# DM3370_EEPROM_Add.net
KiCad netlist of a schematic drawn in Altium Designer
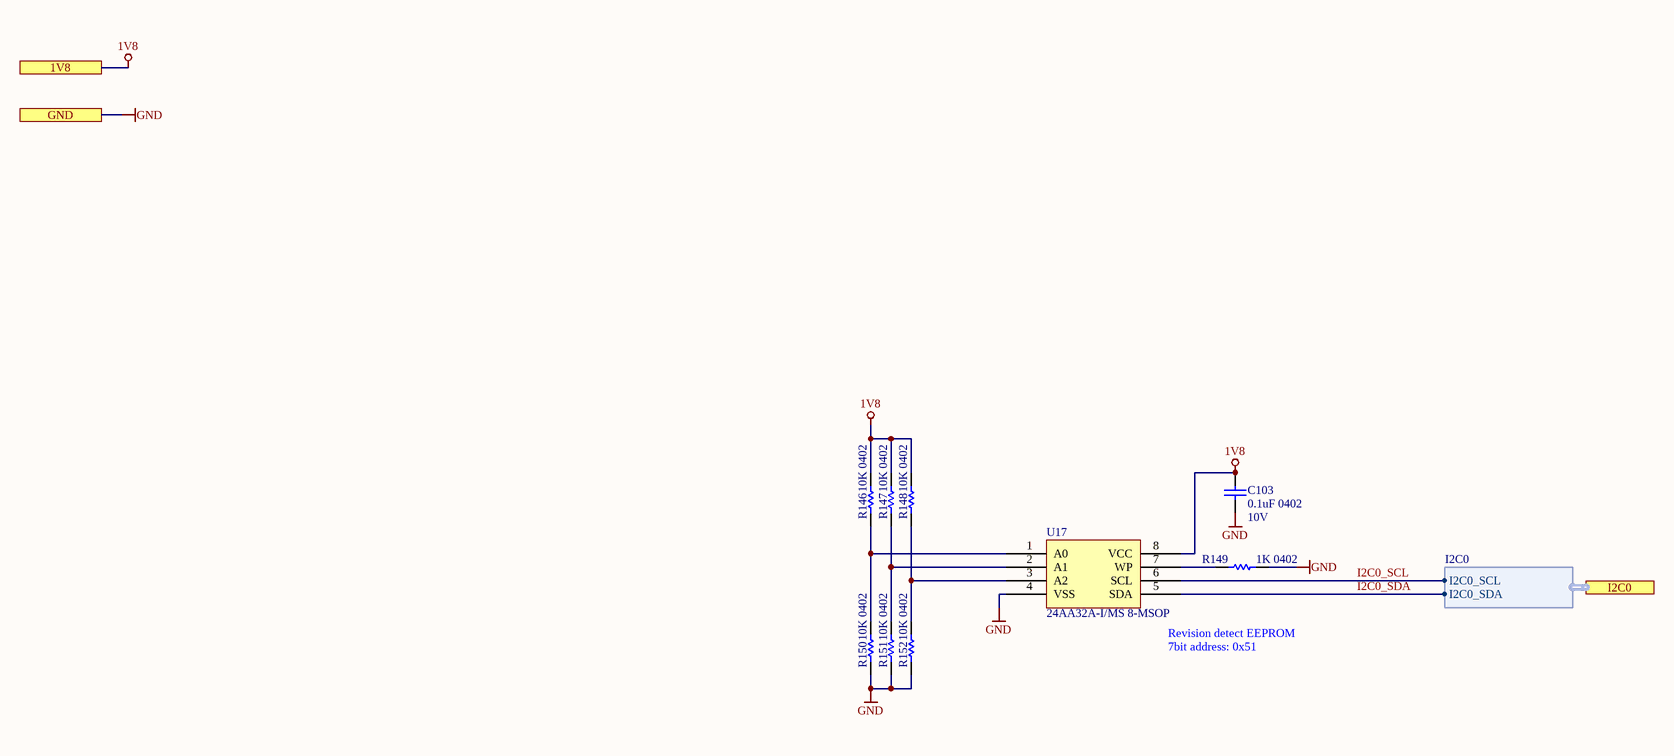
[diagram p0: DM3370_EEPROM_Add.SchDoc]

(export (version "E")
  (design (tool "Eeschema 10.0.6"))
  (components
    (comp (ref "C103")
      (value "0.1uF 0402")
      (footprint "CAP_Altium_Vault_Generic:CAPC0402(1005)70_L")
      (description "CAP CER 0.1UF 10V X7R 0402 5%")
      (fields (field (name "TOLERANCE") "5%") (field (name "VOLTAGE RATING") "10V"))
      (libsource (lib "LuxonisMaster") (part "GRM155R71A104JA01D"))
    )
    (comp (ref "R146")
      (value "10K 0402")
      (footprint "RES_Altium_Vault_Generic:RESC0402(1005)_L")
      (fields (field (name "TOLERANCE") "1%"))
      (libsource (lib "LuxonisMaster") (part "RC0402FR-1310KL"))
    )
    (comp (ref "R147")
      (value "10K 0402")
      (footprint "RES_Altium_Vault_Generic:RESC0402(1005)_L")
      (fields (field (name "TOLERANCE") "1%"))
      (libsource (lib "LuxonisMaster") (part "RC0402FR-1310KL"))
    )
    (comp (ref "R148")
      (value "10K 0402")
      (footprint "RES_Altium_Vault_Generic:RESC0402(1005)_L")
      (fields (field (name "TOLERANCE") "1%"))
      (libsource (lib "LuxonisMaster") (part "RC0402FR-1310KL"))
    )
    (comp (ref "R149")
      (value "1K 0402")
      (footprint "RES_Altium_Vault_Generic:RESC0402(1005)_L")
      (description "RES SMD 1K OHM 1% 1/16W 0402")
      (fields (field (name "TOLERANCE") "1%"))
      (libsource (lib "LuxonisMaster") (part "RC0402FR-071KL"))
    )
    (comp (ref "R150")
      (value "10K 0402")
      (footprint "RES_Altium_Vault_Generic:RESC0402(1005)_L")
      (fields (field (name "TOLERANCE") "1%"))
      (libsource (lib "LuxonisMaster") (part "RC0402FR-1310KL"))
    )
    (comp (ref "R151")
      (value "10K 0402")
      (footprint "RES_Altium_Vault_Generic:RESC0402(1005)_L")
      (fields (field (name "TOLERANCE") "1%"))
      (libsource (lib "LuxonisMaster") (part "RC0402FR-1310KL"))
    )
    (comp (ref "R152")
      (value "10K 0402")
      (footprint "RES_Altium_Vault_Generic:RESC0402(1005)_L")
      (fields (field (name "TOLERANCE") "1%"))
      (libsource (lib "LuxonisMaster") (part "RC0402FR-1310KL"))
    )
    (comp (ref "U17")
      (value "24AA32A-I/MS 8-MSOP")
      (footprint "LuxonisMaster:24AA32A-I/MS")
      (description "IC EEPROM 32K I2C 400KHZ 8MSOP Memory IC 32Kb (4K x 8) I²C 400kHz 900ns 8-MSOP")
      (libsource (lib "LuxonisMaster") (part "24AA32A-I/MS"))
    )
  )
  (nets
    (net (code "2") (name "/I2C0_SCL") (class "Default")
      (node (ref "U17") (pin "6") (pinfunction "SCL_6") (pintype "passive"))
    )
    (net (code "3") (name "/I2C0_SDA") (class "Default")
      (node (ref "U17") (pin "5") (pinfunction "SDA_5") (pintype "passive"))
    )
    (net (code "5") (name "1V8") (class "Default")
      (node (ref "C103") (pin "2") (pinfunction "2_2") (pintype "passive"))
      (node (ref "R146") (pin "2") (pinfunction "2_2") (pintype "passive"))
      (node (ref "R147") (pin "2") (pinfunction "2_2") (pintype "passive"))
      (node (ref "R148") (pin "2") (pinfunction "2_2") (pintype "passive"))
      (node (ref "U17") (pin "8") (pinfunction "VCC_8") (pintype "passive"))
    )
    (net (code "6") (name "GND") (class "Default")
      (node (ref "C103") (pin "1") (pinfunction "1_1") (pintype "passive"))
      (node (ref "R149") (pin "1") (pinfunction "1_1") (pintype "passive"))
      (node (ref "R150") (pin "1") (pinfunction "1_1") (pintype "passive"))
      (node (ref "R151") (pin "1") (pinfunction "1_1") (pintype "passive"))
      (node (ref "R152") (pin "1") (pinfunction "1_1") (pintype "passive"))
      (node (ref "U17") (pin "4") (pinfunction "VSS_4") (pintype "passive"))
    )
    (net (code "7") (name "Net-(U17-A0)") (class "Default")
      (node (ref "R146") (pin "1") (pinfunction "1_1") (pintype "passive"))
      (node (ref "R150") (pin "2") (pinfunction "2_2") (pintype "passive"))
      (node (ref "U17") (pin "1") (pinfunction "A0_1") (pintype "passive"))
    )
    (net (code "8") (name "Net-(U17-A1)") (class "Default")
      (node (ref "R147") (pin "1") (pinfunction "1_1") (pintype "passive"))
      (node (ref "R151") (pin "2") (pinfunction "2_2") (pintype "passive"))
      (node (ref "U17") (pin "2") (pinfunction "A1_2") (pintype "passive"))
    )
    (net (code "9") (name "Net-(U17-A2)") (class "Default")
      (node (ref "R148") (pin "1") (pinfunction "1_1") (pintype "passive"))
      (node (ref "R152") (pin "2") (pinfunction "2_2") (pintype "passive"))
      (node (ref "U17") (pin "3") (pinfunction "A2_3") (pintype "passive"))
    )
    (net (code "10") (name "Net-(U17-WP)") (class "Default")
      (node (ref "R149") (pin "2") (pinfunction "2_2") (pintype "passive"))
      (node (ref "U17") (pin "7") (pinfunction "WP_7") (pintype "passive"))
    )
  )
)
